# Interfaces_and_Connectors_-_Sensors.net
KiCad netlist of a schematic drawn in Altium Designer
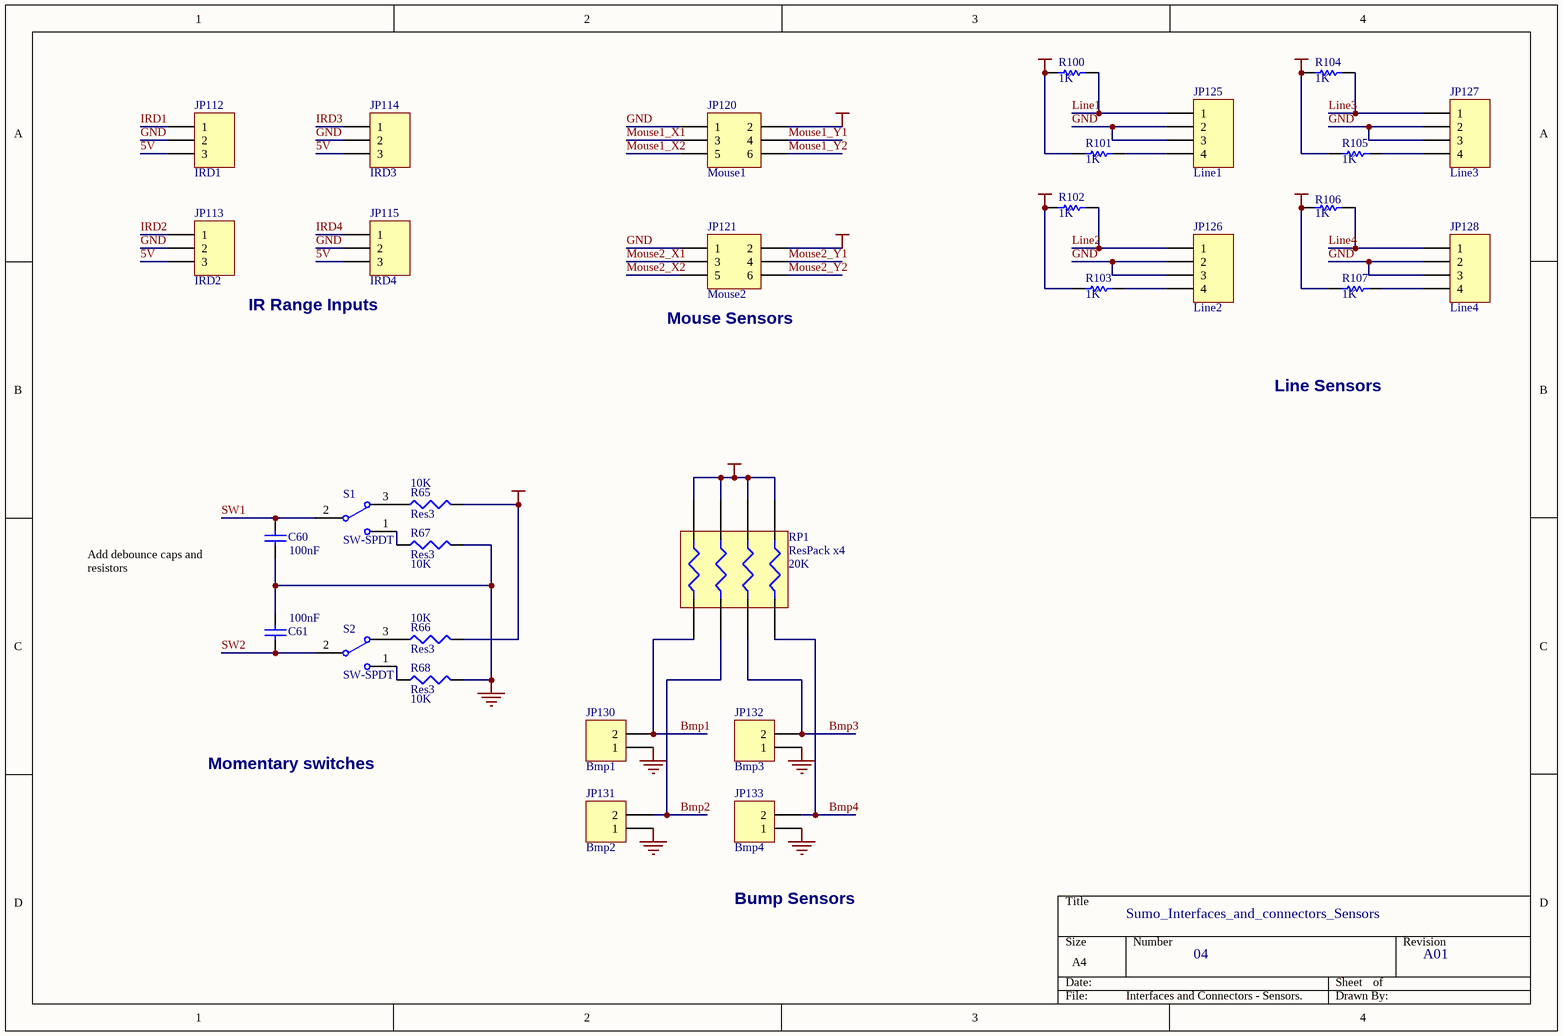
[diagram p0: Interfaces and Connectors - Sensors.SCHDOC]

(export (version "E")
  (design (tool "Eeschema 10.0.6"))
  (components
    (comp (ref "C60")
      (value "100nF")
      (footprint "CR2012-0805")
      (description "Capacitor (Semiconductor SIM Model)")
      (fields (field (name "Comment") "Cap Semi") (field (name "PUBLISHER") "Altium Limited"))
      (libsource (lib "Miscellaneous Devices") (part "Cap Semi"))
    )
    (comp (ref "C61")
      (value "100nF")
      (footprint "CR2012-0805")
      (description "Capacitor (Semiconductor SIM Model)")
      (fields (field (name "Comment") "Cap Semi") (field (name "PUBLISHER") "Altium Limited"))
      (libsource (lib "Miscellaneous Devices") (part "Cap Semi"))
    )
    (comp (ref "JP112")
      (value "IRD1")
      (footprint "ZHR 1x3 1.5mm")
      (description "Header, 3-Pin")
      (fields (field (name "PUBLISHER") "Altium Limited"))
      (libsource (lib "Miscellaneous Connectors") (part "MHDR1X3"))
    )
    (comp (ref "JP113")
      (value "IRD2")
      (footprint "ZHR 1x3 1.5mm")
      (description "Header, 3-Pin")
      (fields (field (name "PUBLISHER") "Altium Limited"))
      (libsource (lib "Miscellaneous Connectors") (part "MHDR1X3"))
    )
    (comp (ref "JP114")
      (value "IRD3")
      (footprint "ZHR 1x3 1.5mm")
      (description "Header, 3-Pin")
      (fields (field (name "PUBLISHER") "Altium Limited"))
      (libsource (lib "Miscellaneous Connectors") (part "MHDR1X3"))
    )
    (comp (ref "JP115")
      (value "IRD4")
      (footprint "ZHR 1x3 1.5mm")
      (description "Header, 3-Pin")
      (fields (field (name "PUBLISHER") "Altium Limited"))
      (libsource (lib "Miscellaneous Connectors") (part "MHDR1X3"))
    )
    (comp (ref "JP120")
      (value "Mouse1")
      (footprint "PHR 1x6 2mm")
      (description "Header, 3-Pin, Dual row")
      (fields (field (name "PUBLISHER") "Altium Limited"))
      (libsource (lib "Miscellaneous Connectors") (part "Header 3X2"))
    )
    (comp (ref "JP121")
      (value "Mouse2")
      (footprint "PHR 1x6 2mm")
      (description "Header, 3-Pin, Dual row")
      (fields (field (name "PUBLISHER") "Altium Limited"))
      (libsource (lib "Miscellaneous Connectors") (part "Header 3X2"))
    )
    (comp (ref "JP125")
      (value "Line1")
      (footprint "EHR 1x4 2.5mm")
      (description "Header, 4-Pin, Right Angle")
      (fields (field (name "PUBLISHER") "Altium Limited"))
      (libsource (lib "Miscellaneous Connectors") (part "Header 4H"))
    )
    (comp (ref "JP126")
      (value "Line2")
      (footprint "EHR 1x4 2.5mm")
      (description "Header, 4-Pin, Right Angle")
      (fields (field (name "PUBLISHER") "Altium Limited"))
      (libsource (lib "Miscellaneous Connectors") (part "Header 4H"))
    )
    (comp (ref "JP127")
      (value "Line3")
      (footprint "EHR 1x4 2.5mm")
      (description "Header, 4-Pin, Right Angle")
      (fields (field (name "PUBLISHER") "Altium Limited"))
      (libsource (lib "Miscellaneous Connectors") (part "Header 4H"))
    )
    (comp (ref "JP128")
      (value "Line4")
      (footprint "EHR 1x4 2.5mm")
      (description "Header, 4-Pin, Right Angle")
      (fields (field (name "PUBLISHER") "Altium Limited"))
      (libsource (lib "Miscellaneous Connectors") (part "Header 4H"))
    )
    (comp (ref "JP130")
      (value "Bmp1")
      (footprint "KK 1x2 2.54mm")
      (description "Header, 2-Pin")
      (fields (field (name "PUBLISHER") "Altium Limited"))
      (libsource (lib "Miscellaneous Connectors") (part "Header 2"))
    )
    (comp (ref "JP131")
      (value "Bmp2")
      (footprint "KK 1x2 2.54mm")
      (description "Header, 2-Pin")
      (fields (field (name "PUBLISHER") "Altium Limited"))
      (libsource (lib "Miscellaneous Connectors") (part "Header 2"))
    )
    (comp (ref "JP132")
      (value "Bmp3")
      (footprint "KK 1x2 2.54mm")
      (description "Header, 2-Pin")
      (fields (field (name "PUBLISHER") "Altium Limited"))
      (libsource (lib "Miscellaneous Connectors") (part "Header 2"))
    )
    (comp (ref "JP133")
      (value "Bmp4")
      (footprint "KK 1x2 2.54mm")
      (description "Header, 2-Pin")
      (fields (field (name "PUBLISHER") "Altium Limited"))
      (libsource (lib "Miscellaneous Connectors") (part "Header 2"))
    )
    (comp (ref "R65")
      (value "Res3")
      (footprint "R2012-0805")
      (description "Resistor")
      (fields (field (name "ALTIUM_VALUE") "10K") (field (name "PUBLISHER") "Altium Limited"))
      (libsource (lib "Miscellaneous Devices") (part "Res3"))
    )
    (comp (ref "R66")
      (value "Res3")
      (footprint "R2012-0805")
      (description "Resistor")
      (fields (field (name "ALTIUM_VALUE") "10K") (field (name "PUBLISHER") "Altium Limited"))
      (libsource (lib "Miscellaneous Devices") (part "Res3"))
    )
    (comp (ref "R67")
      (value "Res3")
      (footprint "R2012-0805")
      (description "Resistor")
      (fields (field (name "ALTIUM_VALUE") "10K") (field (name "PUBLISHER") "Altium Limited"))
      (libsource (lib "Miscellaneous Devices") (part "Res3"))
    )
    (comp (ref "R68")
      (value "Res3")
      (footprint "R2012-0805")
      (description "Resistor")
      (fields (field (name "ALTIUM_VALUE") "10K") (field (name "PUBLISHER") "Altium Limited"))
      (libsource (lib "Miscellaneous Devices") (part "Res3"))
    )
    (comp (ref "R100")
      (value "1K")
      (footprint "R2012-0805")
      (description "Resistor")
      (fields (field (name "Comment") "Res1") (field (name "PUBLISHER") "Altium Limited"))
      (libsource (lib "Miscellaneous Devices") (part "Res1"))
    )
    (comp (ref "R101")
      (value "1K")
      (footprint "R2012-0805")
      (description "Resistor")
      (fields (field (name "Comment") "Res1") (field (name "PUBLISHER") "Altium Limited"))
      (libsource (lib "Miscellaneous Devices") (part "Res1"))
    )
    (comp (ref "R102")
      (value "1K")
      (footprint "R2012-0805")
      (description "Resistor")
      (fields (field (name "Comment") "Res1") (field (name "PUBLISHER") "Altium Limited"))
      (libsource (lib "Miscellaneous Devices") (part "Res1"))
    )
    (comp (ref "R103")
      (value "1K")
      (footprint "R2012-0805")
      (description "Resistor")
      (fields (field (name "Comment") "Res1") (field (name "PUBLISHER") "Altium Limited"))
      (libsource (lib "Miscellaneous Devices") (part "Res1"))
    )
    (comp (ref "R104")
      (value "1K")
      (footprint "R2012-0805")
      (description "Resistor")
      (fields (field (name "Comment") "Res1") (field (name "PUBLISHER") "Altium Limited"))
      (libsource (lib "Miscellaneous Devices") (part "Res1"))
    )
    (comp (ref "R105")
      (value "1K")
      (footprint "R2012-0805")
      (description "Resistor")
      (fields (field (name "Comment") "Res1") (field (name "PUBLISHER") "Altium Limited"))
      (libsource (lib "Miscellaneous Devices") (part "Res1"))
    )
    (comp (ref "R106")
      (value "1K")
      (footprint "R2012-0805")
      (description "Resistor")
      (fields (field (name "Comment") "Res1") (field (name "PUBLISHER") "Altium Limited"))
      (libsource (lib "Miscellaneous Devices") (part "Res1"))
    )
    (comp (ref "R107")
      (value "1K")
      (footprint "R2012-0805")
      (description "Resistor")
      (fields (field (name "Comment") "Res1") (field (name "PUBLISHER") "Altium Limited"))
      (libsource (lib "Miscellaneous Devices") (part "Res1"))
    )
    (comp (ref "RP1")
      (value "ResPack x4")
      (footprint "4x0603 Resistor pack")
      (fields (field (name "ALTIUM_VALUE") "20K"))
      (libsource (lib "Sumo") (part "ResPack x4"))
    )
    (comp (ref "S1")
      (value "SW-SPDT")
      (footprint "SW SPDT")
      (description "SPDT Subminiature Toggle Switch, Right Angle Mounting, Vertical Actuation")
      (fields (field (name "PUBLISHER") "Altium Limited"))
      (libsource (lib "Miscellaneous Devices") (part "SW-SPDT"))
    )
    (comp (ref "S2")
      (value "SW-SPDT")
      (footprint "SW SPDT")
      (description "SPDT Subminiature Toggle Switch, Right Angle Mounting, Vertical Actuation")
      (fields (field (name "PUBLISHER") "Altium Limited"))
      (libsource (lib "Miscellaneous Devices") (part "SW-SPDT"))
    )
  )
  (nets
    (net (code "1") (name "/Bmp1") (class "Default")
      (node (ref "JP130") (pin "2") (pinfunction "2_2") (pintype "passive"))
      (node (ref "RP1") (pin "1") (pintype "passive"))
    )
    (net (code "2") (name "/Bmp2") (class "Default")
      (node (ref "JP131") (pin "2") (pinfunction "2_2") (pintype "passive"))
      (node (ref "RP1") (pin "2") (pintype "passive"))
    )
    (net (code "3") (name "/Bmp3") (class "Default")
      (node (ref "JP132") (pin "2") (pinfunction "2_2") (pintype "passive"))
      (node (ref "RP1") (pin "3") (pintype "passive"))
    )
    (net (code "4") (name "/Bmp4") (class "Default")
      (node (ref "JP133") (pin "2") (pinfunction "2_2") (pintype "passive"))
      (node (ref "RP1") (pin "4") (pintype "passive"))
    )
    (net (code "5") (name "/IRD1") (class "Default")
      (node (ref "JP112") (pin "1") (pinfunction "1_1") (pintype "passive"))
    )
    (net (code "6") (name "/IRD2") (class "Default")
      (node (ref "JP113") (pin "1") (pinfunction "1_1") (pintype "passive"))
    )
    (net (code "7") (name "/IRD3") (class "Default")
      (node (ref "JP114") (pin "1") (pinfunction "1_1") (pintype "passive"))
    )
    (net (code "8") (name "/IRD4") (class "Default")
      (node (ref "JP115") (pin "1") (pinfunction "1_1") (pintype "passive"))
    )
    (net (code "9") (name "/Line1") (class "Default")
      (node (ref "JP125") (pin "1") (pinfunction "1_1") (pintype "passive"))
      (node (ref "R100") (pin "2") (pinfunction "2_2") (pintype "passive"))
    )
    (net (code "10") (name "/Line2") (class "Default")
      (node (ref "JP126") (pin "1") (pinfunction "1_1") (pintype "passive"))
      (node (ref "R102") (pin "2") (pinfunction "2_2") (pintype "passive"))
    )
    (net (code "11") (name "/Line3") (class "Default")
      (node (ref "JP127") (pin "1") (pinfunction "1_1") (pintype "passive"))
      (node (ref "R104") (pin "2") (pinfunction "2_2") (pintype "passive"))
    )
    (net (code "12") (name "/Line4") (class "Default")
      (node (ref "JP128") (pin "1") (pinfunction "1_1") (pintype "passive"))
      (node (ref "R106") (pin "2") (pinfunction "2_2") (pintype "passive"))
    )
    (net (code "13") (name "/Mouse1_X1") (class "Default")
      (node (ref "JP120") (pin "3") (pinfunction "3_3") (pintype "passive"))
    )
    (net (code "14") (name "/Mouse1_X2") (class "Default")
      (node (ref "JP120") (pin "5") (pinfunction "5_5") (pintype "passive"))
    )
    (net (code "15") (name "/Mouse1_Y1") (class "Default")
      (node (ref "JP120") (pin "4") (pinfunction "4_4") (pintype "passive"))
    )
    (net (code "16") (name "/Mouse1_Y2") (class "Default")
      (node (ref "JP120") (pin "6") (pinfunction "6_6") (pintype "passive"))
    )
    (net (code "17") (name "/Mouse2_X1") (class "Default")
      (node (ref "JP121") (pin "3") (pinfunction "3_3") (pintype "passive"))
    )
    (net (code "18") (name "/Mouse2_X2") (class "Default")
      (node (ref "JP121") (pin "5") (pinfunction "5_5") (pintype "passive"))
    )
    (net (code "19") (name "/Mouse2_Y1") (class "Default")
      (node (ref "JP121") (pin "4") (pinfunction "4_4") (pintype "passive"))
    )
    (net (code "20") (name "/Mouse2_Y2") (class "Default")
      (node (ref "JP121") (pin "6") (pinfunction "6_6") (pintype "passive"))
    )
    (net (code "21") (name "/SW1") (class "Default")
      (node (ref "C60") (pin "2") (pinfunction "2_2") (pintype "passive"))
      (node (ref "S1") (pin "2") (pintype "passive"))
    )
    (net (code "22") (name "/SW2") (class "Default")
      (node (ref "C61") (pin "1") (pinfunction "1_1") (pintype "passive"))
      (node (ref "S2") (pin "2") (pintype "passive"))
    )
    (net (code "23") (name "5V") (class "Default")
      (node (ref "JP112") (pin "3") (pinfunction "3_3") (pintype "passive"))
      (node (ref "JP113") (pin "3") (pinfunction "3_3") (pintype "passive"))
      (node (ref "JP114") (pin "3") (pinfunction "3_3") (pintype "passive"))
      (node (ref "JP115") (pin "3") (pinfunction "3_3") (pintype "passive"))
      (node (ref "JP120") (pin "2") (pinfunction "2_2") (pintype "passive"))
      (node (ref "JP121") (pin "2") (pinfunction "2_2") (pintype "passive"))
      (node (ref "R100") (pin "1") (pinfunction "1_1") (pintype "passive"))
      (node (ref "R101") (pin "1") (pinfunction "1_1") (pintype "passive"))
      (node (ref "R102") (pin "1") (pinfunction "1_1") (pintype "passive"))
      (node (ref "R103") (pin "1") (pinfunction "1_1") (pintype "passive"))
      (node (ref "R104") (pin "1") (pinfunction "1_1") (pintype "passive"))
      (node (ref "R105") (pin "1") (pinfunction "1_1") (pintype "passive"))
      (node (ref "R106") (pin "1") (pinfunction "1_1") (pintype "passive"))
      (node (ref "R107") (pin "1") (pinfunction "1_1") (pintype "passive"))
      (node (ref "R65") (pin "2") (pinfunction "2_2") (pintype "passive"))
      (node (ref "R66") (pin "2") (pinfunction "2_2") (pintype "passive"))
      (node (ref "RP1") (pin "5") (pintype "passive"))
      (node (ref "RP1") (pin "6") (pintype "passive"))
      (node (ref "RP1") (pin "7") (pintype "passive"))
      (node (ref "RP1") (pin "8") (pintype "passive"))
    )
    (net (code "24") (name "GND") (class "Default")
      (node (ref "C60") (pin "1") (pinfunction "1_1") (pintype "passive"))
      (node (ref "C61") (pin "2") (pinfunction "2_2") (pintype "passive"))
      (node (ref "JP112") (pin "2") (pinfunction "2_2") (pintype "passive"))
      (node (ref "JP113") (pin "2") (pinfunction "2_2") (pintype "passive"))
      (node (ref "JP114") (pin "2") (pinfunction "2_2") (pintype "passive"))
      (node (ref "JP115") (pin "2") (pinfunction "2_2") (pintype "passive"))
      (node (ref "JP120") (pin "1") (pinfunction "1_1") (pintype "passive"))
      (node (ref "JP121") (pin "1") (pinfunction "1_1") (pintype "passive"))
      (node (ref "JP125") (pin "2") (pinfunction "2_2") (pintype "passive"))
      (node (ref "JP125") (pin "3") (pinfunction "3_3") (pintype "passive"))
      (node (ref "JP126") (pin "2") (pinfunction "2_2") (pintype "passive"))
      (node (ref "JP126") (pin "3") (pinfunction "3_3") (pintype "passive"))
      (node (ref "JP127") (pin "2") (pinfunction "2_2") (pintype "passive"))
      (node (ref "JP127") (pin "3") (pinfunction "3_3") (pintype "passive"))
      (node (ref "JP128") (pin "2") (pinfunction "2_2") (pintype "passive"))
      (node (ref "JP128") (pin "3") (pinfunction "3_3") (pintype "passive"))
      (node (ref "JP130") (pin "1") (pinfunction "1_1") (pintype "passive"))
      (node (ref "JP131") (pin "1") (pinfunction "1_1") (pintype "passive"))
      (node (ref "JP132") (pin "1") (pinfunction "1_1") (pintype "passive"))
      (node (ref "JP133") (pin "1") (pinfunction "1_1") (pintype "passive"))
      (node (ref "R67") (pin "2") (pinfunction "2_2") (pintype "passive"))
      (node (ref "R68") (pin "2") (pinfunction "2_2") (pintype "passive"))
    )
    (net (code "25") (name "Net-(JP125-Pad4)") (class "Default")
      (node (ref "JP125") (pin "4") (pinfunction "4_4") (pintype "passive"))
      (node (ref "R101") (pin "2") (pinfunction "2_2") (pintype "passive"))
    )
    (net (code "26") (name "Net-(JP126-Pad4)") (class "Default")
      (node (ref "JP126") (pin "4") (pinfunction "4_4") (pintype "passive"))
      (node (ref "R103") (pin "2") (pinfunction "2_2") (pintype "passive"))
    )
    (net (code "27") (name "Net-(JP127-Pad4)") (class "Default")
      (node (ref "JP127") (pin "4") (pinfunction "4_4") (pintype "passive"))
      (node (ref "R105") (pin "2") (pinfunction "2_2") (pintype "passive"))
    )
    (net (code "28") (name "Net-(JP128-Pad4)") (class "Default")
      (node (ref "JP128") (pin "4") (pinfunction "4_4") (pintype "passive"))
      (node (ref "R107") (pin "2") (pinfunction "2_2") (pintype "passive"))
    )
    (net (code "29") (name "Net-(R65-Pad1)") (class "Default")
      (node (ref "R65") (pin "1") (pinfunction "1_1") (pintype "passive"))
      (node (ref "S1") (pin "3") (pintype "passive"))
    )
    (net (code "30") (name "Net-(R66-Pad1)") (class "Default")
      (node (ref "R66") (pin "1") (pinfunction "1_1") (pintype "passive"))
      (node (ref "S2") (pin "3") (pintype "passive"))
    )
    (net (code "31") (name "Net-(R67-Pad1)") (class "Default")
      (node (ref "R67") (pin "1") (pinfunction "1_1") (pintype "passive"))
      (node (ref "S1") (pin "1") (pintype "passive"))
    )
    (net (code "32") (name "Net-(R68-Pad1)") (class "Default")
      (node (ref "R68") (pin "1") (pinfunction "1_1") (pintype "passive"))
      (node (ref "S2") (pin "1") (pintype "passive"))
    )
  )
)
